# cargador3.net
KiCad netlist of a schematic drawn in EAGLE
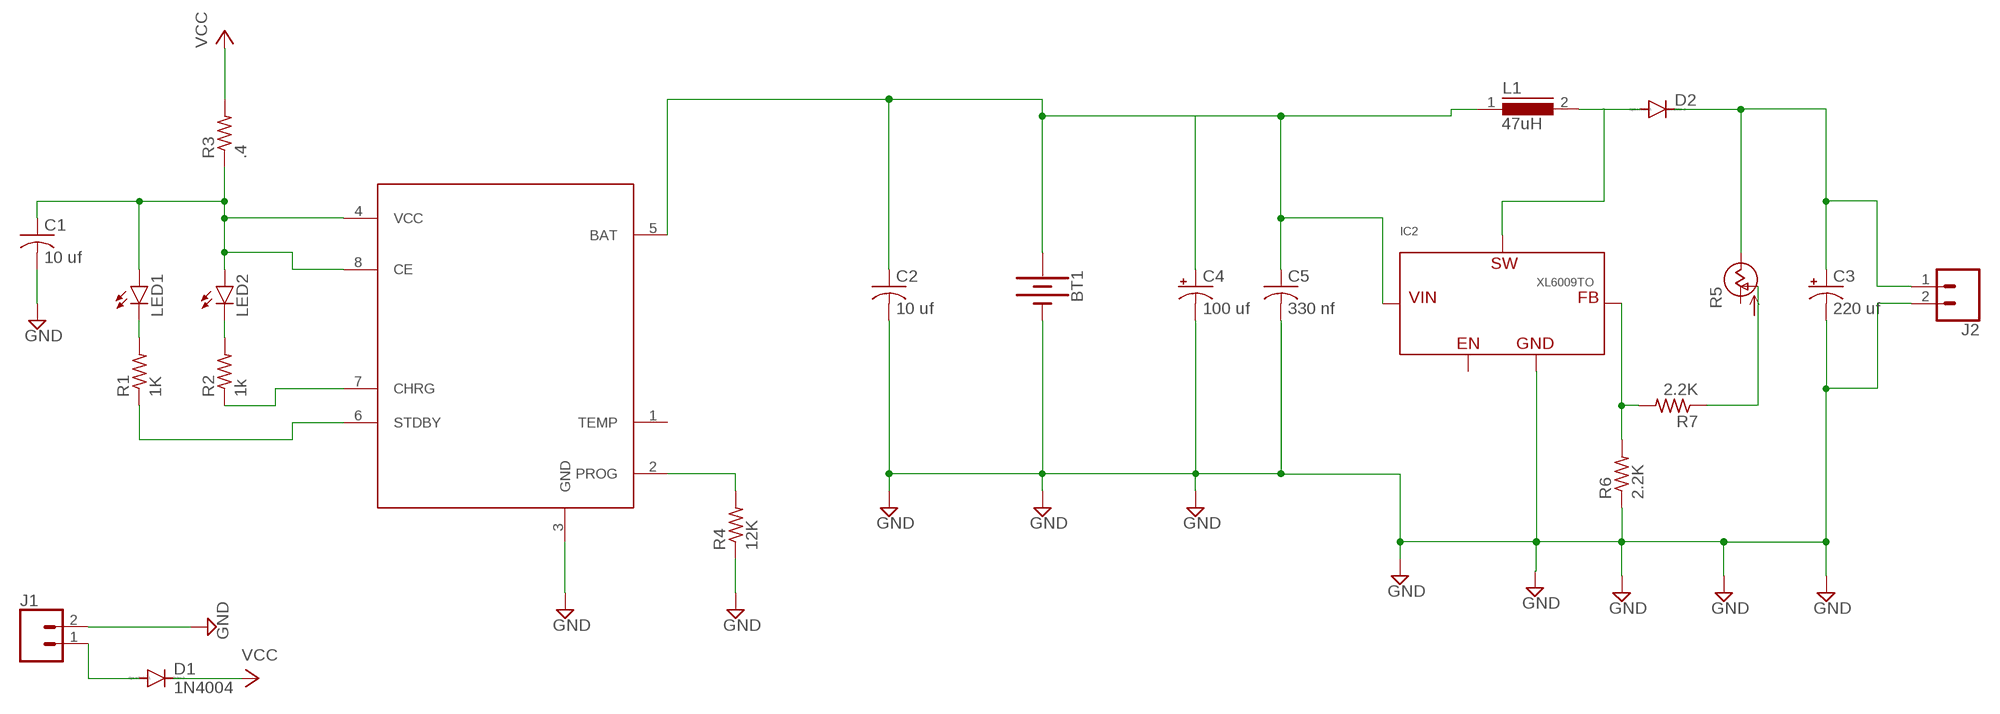
[diagram p0: schematic, sheet 1]

(export (version "E")
  (design (tool "Eeschema 10.0.6"))
  (components
    (comp (ref "BT1")
      (value "BATTERY-18650")
      (footprint "eagle-import:BATTERY_18650-HOLDER")
      (libsource (lib "eagle-import") (part "BATTERY-18650"))
    )
    (comp (ref "C1")
      (value "10 uf")
      (footprint "eagle-import:C0402")
      (libsource (lib "eagle-import") (part "C-USC0402"))
    )
    (comp (ref "C2")
      (value "10 uf")
      (footprint "eagle-import:C0402")
      (libsource (lib "eagle-import") (part "C-USC0402"))
    )
    (comp (ref "C3")
      (value "220 uf")
      (footprint "eagle-import:140CLH-1010")
      (fields (field (name "SPICEPREFIX") "C"))
      (libsource (lib "eagle-import") (part "CPOL-US140CLH-1010"))
    )
    (comp (ref "C4")
      (value "100 uf")
      (footprint "eagle-import:140CLH-1010")
      (libsource (lib "eagle-import") (part "CPOL-US140CLH-1010"))
    )
    (comp (ref "C5")
      (value "330 nf")
      (footprint "eagle-import:C0805")
      (libsource (lib "eagle-import") (part "C-USC0805"))
    )
    (comp (ref "D1")
      (value "1N4004")
      (footprint "eagle-import:DO41-10")
      (libsource (lib "eagle-import") (part "1N4004"))
    )
    (comp (ref "D2")
      (value "DIODE-DO214AA")
      (footprint "eagle-import:DO214AA")
      (libsource (lib "eagle-import") (part "DIODE-DO214AA"))
    )
    (comp (ref "IC2")
      (value "XL6009TO")
      (footprint "eagle-import:TO263-5L")
      (libsource (lib "eagle-import") (part "XL6009TO"))
    )
    (comp (ref "J1")
      (value "CONN_02")
      (footprint "eagle-import:1X02")
      (libsource (lib "eagle-import") (part "CONN_02"))
    )
    (comp (ref "J2")
      (value "CONN_02")
      (footprint "eagle-import:1X02")
      (libsource (lib "eagle-import") (part "CONN_02"))
    )
    (comp (ref "L1")
      (value "47uH")
      (footprint "eagle-import:SRR1210")
      (libsource (lib "eagle-import") (part "SRR1210"))
    )
    (comp (ref "LED1")
      (value "LEDSMART-LED")
      (footprint "eagle-import:SMART-LED")
      (libsource (lib "eagle-import") (part "LEDSMART-LED"))
    )
    (comp (ref "LED2")
      (value "LEDSMART-LED")
      (footprint "eagle-import:SMART-LED")
      (libsource (lib "eagle-import") (part "LEDSMART-LED"))
    )
    (comp (ref "R1")
      (value "1K")
      (footprint "eagle-import:R1206")
      (libsource (lib "eagle-import") (part "R-US_R1206"))
    )
    (comp (ref "R2")
      (value "1k")
      (footprint "eagle-import:R1206")
      (libsource (lib "eagle-import") (part "R-US_R1206"))
    )
    (comp (ref "R3")
      (value ".4")
      (footprint "eagle-import:R2010")
      (libsource (lib "eagle-import") (part "R-US_R2010"))
    )
    (comp (ref "R4")
      (value "12K")
      (footprint "eagle-import:R0402")
      (libsource (lib "eagle-import") (part "R-US_R0402"))
    )
    (comp (ref "R5")
      (value "POTTRB64Y")
      (footprint "eagle-import:B64Y")
      (libsource (lib "eagle-import") (part "POTTRB64Y"))
    )
    (comp (ref "R6")
      (value "2.2K")
      (footprint "eagle-import:R2010")
      (libsource (lib "eagle-import") (part "R-US_R2010"))
    )
    (comp (ref "R7")
      (value "2.2K")
      (footprint "eagle-import:R2010")
      (libsource (lib "eagle-import") (part "R-US_R2010"))
    )
    (comp (ref "TC4056")
      (value "TC4056A")
      (footprint "eagle-import:TC4056A")
      (libsource (lib "eagle-import") (part "TC4056A"))
    )
  )
  (nets
    (net (code "1") (name "GND") (class "Default")
      (node (ref "BT1") (pin "GND@1") (pinfunction "-_GND@1") (pintype "power_in"))
      (node (ref "C1") (pin "2") (pinfunction "2_2") (pintype "passive"))
      (node (ref "C2") (pin "2") (pinfunction "2_2") (pintype "passive"))
      (node (ref "C3") (pin "-") (pinfunction "-_-") (pintype "passive"))
      (node (ref "C4") (pin "-") (pinfunction "-_-") (pintype "passive"))
      (node (ref "C5") (pin "2") (pinfunction "2_2") (pintype "passive"))
      (node (ref "IC2") (pin "1") (pinfunction "GND_1") (pintype "bidirectional"))
      (node (ref "J1") (pin "2") (pinfunction "2_2") (pintype "passive"))
      (node (ref "J2") (pin "2") (pinfunction "2_2") (pintype "passive"))
      (node (ref "R4") (pin "1") (pinfunction "1_1") (pintype "passive"))
      (node (ref "R6") (pin "1") (pinfunction "1_1") (pintype "passive"))
      (node (ref "TC4056") (pin "3") (pinfunction "GND_3") (pintype "bidirectional"))
    )
    (net (code "2") (name "Net-(BT1-+)") (class "Default")
      (node (ref "BT1") (pin "PWR@1") (pinfunction "+_PWR@1") (pintype "power_in"))
      (node (ref "C2") (pin "1") (pinfunction "1_1") (pintype "passive"))
      (node (ref "C4") (pin "+") (pinfunction "+_+") (pintype "passive"))
      (node (ref "C5") (pin "1") (pinfunction "1_1") (pintype "passive"))
      (node (ref "IC2") (pin "4") (pinfunction "VIN_4") (pintype "bidirectional"))
      (node (ref "L1") (pin "1") (pinfunction "1_1") (pintype "passive"))
      (node (ref "TC4056") (pin "5") (pinfunction "BAT_5") (pintype "bidirectional"))
    )
    (net (code "3") (name "Net-(D1-PadA)") (class "Default")
      (node (ref "D1") (pin "A") (pinfunction "A_A") (pintype "passive"))
      (node (ref "J1") (pin "1") (pinfunction "1_1") (pintype "passive"))
    )
    (net (code "4") (name "Net-(IC2-FB)") (class "Default")
      (node (ref "IC2") (pin "5") (pinfunction "FB_5") (pintype "bidirectional"))
      (node (ref "R6") (pin "2") (pinfunction "2_2") (pintype "passive"))
      (node (ref "R7") (pin "2") (pinfunction "2_2") (pintype "passive"))
    )
    (net (code "5") (name "Net-(IC2-SW)") (class "Default")
      (node (ref "D2") (pin "A") (pinfunction "A_A") (pintype "passive"))
      (node (ref "IC2") (pin "3") (pinfunction "SW_3") (pintype "bidirectional"))
      (node (ref "L1") (pin "2") (pinfunction "2_2") (pintype "passive"))
    )
    (net (code "6") (name "Net-(LED1-C)") (class "Default")
      (node (ref "LED1") (pin "B") (pinfunction "C_B") (pintype "passive"))
      (node (ref "R1") (pin "2") (pinfunction "2_2") (pintype "passive"))
    )
    (net (code "7") (name "Net-(LED2-C)") (class "Default")
      (node (ref "LED2") (pin "B") (pinfunction "C_B") (pintype "passive"))
      (node (ref "R2") (pin "2") (pinfunction "2_2") (pintype "passive"))
    )
    (net (code "8") (name "Net-(R5-OUT)") (class "Default")
      (node (ref "R5") (pin "S") (pinfunction "OUT_S") (pintype "passive"))
      (node (ref "R7") (pin "1") (pinfunction "1_1") (pintype "passive"))
    )
    (net (code "9") (name "Net-(R5-VSS)") (class "Default")
      (node (ref "C3") (pin "+") (pinfunction "+_+") (pintype "passive"))
      (node (ref "D2") (pin "C") (pinfunction "C_C") (pintype "passive"))
      (node (ref "J2") (pin "1") (pinfunction "1_1") (pintype "passive"))
      (node (ref "R5") (pin "E") (pinfunction "VSS_E") (pintype "passive"))
    )
    (net (code "10") (name "Net-(TC4056-CE)") (class "Default")
      (node (ref "C1") (pin "1") (pinfunction "1_1") (pintype "passive"))
      (node (ref "LED1") (pin "A") (pinfunction "A_A") (pintype "passive"))
      (node (ref "LED2") (pin "A") (pinfunction "A_A") (pintype "passive"))
      (node (ref "R3") (pin "1") (pinfunction "1_1") (pintype "passive"))
      (node (ref "TC4056") (pin "4") (pinfunction "VCC_4") (pintype "bidirectional"))
      (node (ref "TC4056") (pin "8") (pinfunction "CE_8") (pintype "bidirectional"))
    )
    (net (code "11") (name "Net-(TC4056-CHRG)") (class "Default")
      (node (ref "R2") (pin "1") (pinfunction "1_1") (pintype "passive"))
      (node (ref "TC4056") (pin "7") (pinfunction "CHRG_7") (pintype "bidirectional"))
    )
    (net (code "12") (name "Net-(TC4056-PROG)") (class "Default")
      (node (ref "R4") (pin "2") (pinfunction "2_2") (pintype "passive"))
      (node (ref "TC4056") (pin "2") (pinfunction "PROG_2") (pintype "bidirectional"))
    )
    (net (code "13") (name "Net-(TC4056-STDBY)") (class "Default")
      (node (ref "R1") (pin "1") (pinfunction "1_1") (pintype "passive"))
      (node (ref "TC4056") (pin "6") (pinfunction "STDBY_6") (pintype "bidirectional"))
    )
    (net (code "14") (name "VCC") (class "Default")
      (node (ref "D1") (pin "C") (pinfunction "C_C") (pintype "passive"))
      (node (ref "R3") (pin "2") (pinfunction "2_2") (pintype "passive"))
    )
    (net (code "15") (name "unconnected-(IC2-EN-Pad2)") (class "Default")
      (node (ref "IC2") (pin "2") (pinfunction "EN_2") (pintype "bidirectional"))
    )
    (net (code "16") (name "unconnected-(R5-VDD-PadA)") (class "Default")
      (node (ref "R5") (pin "A") (pinfunction "VDD_A") (pintype "passive"))
    )
    (net (code "17") (name "unconnected-(TC4056-TEMP-Pad1)") (class "Default")
      (node (ref "TC4056") (pin "1") (pinfunction "TEMP_1") (pintype "bidirectional"))
    )
  )
)
